# boosterpack.net
KiCad netlist of a schematic drawn in EAGLE
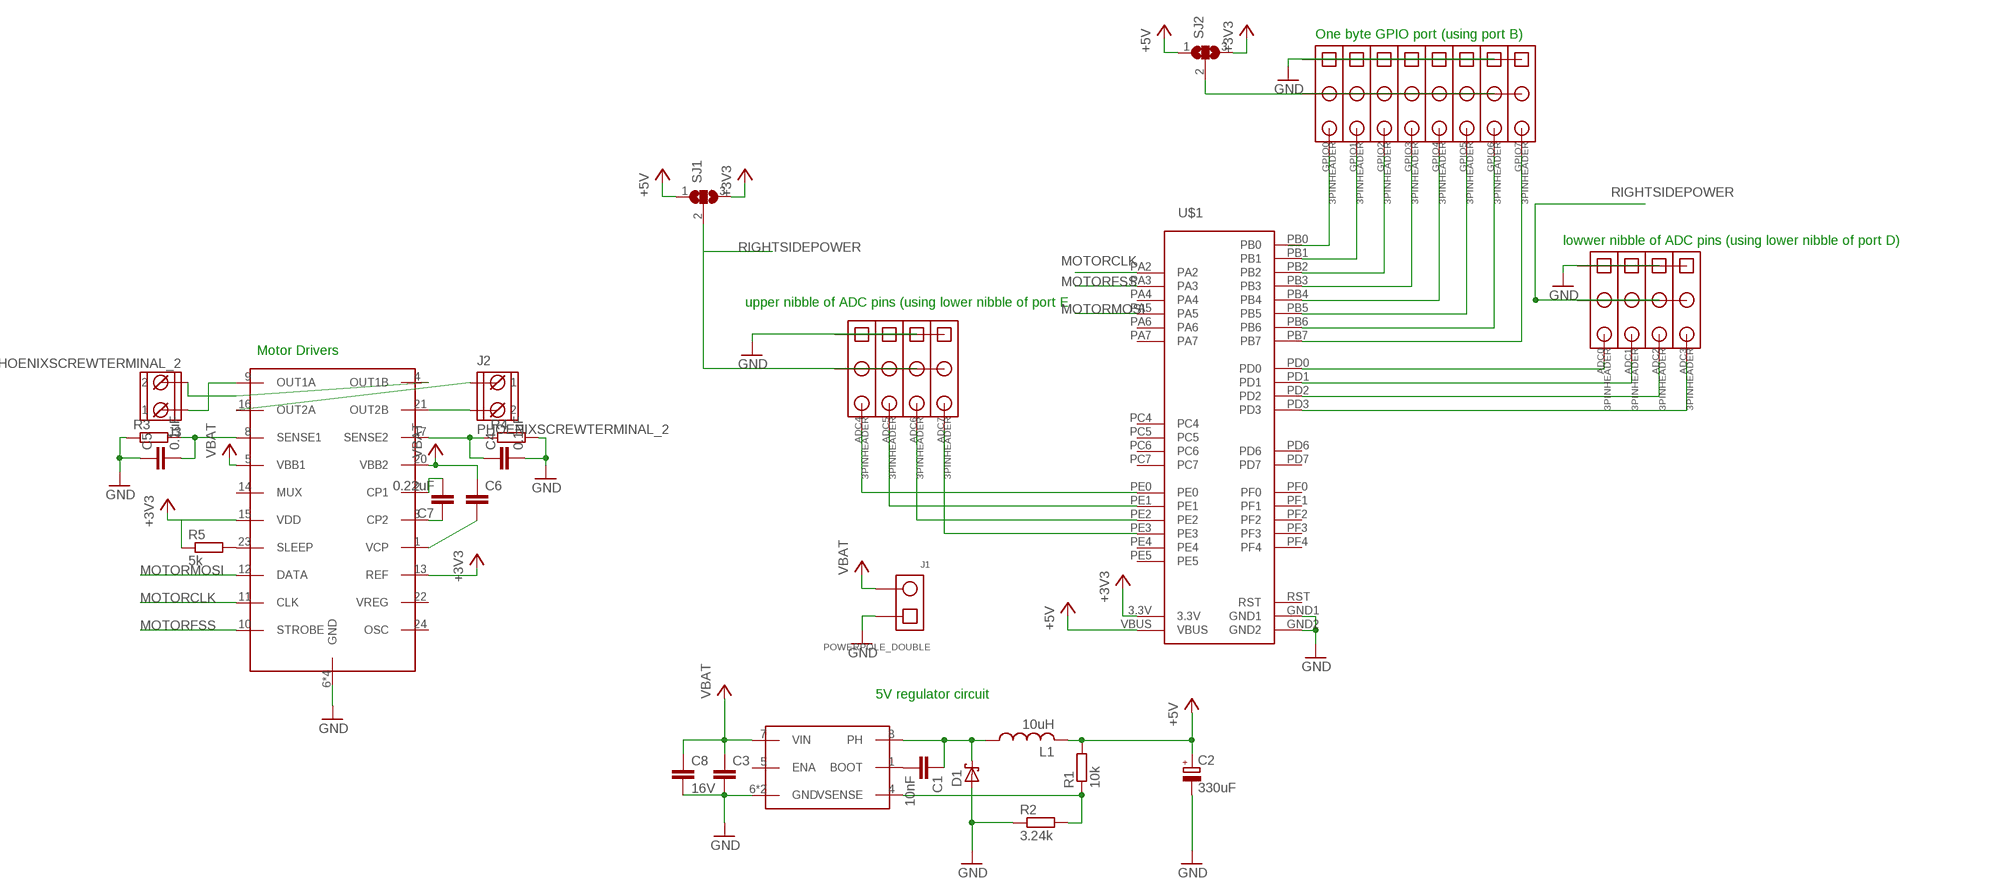
[diagram p0: schematic, sheet 1]

(export (version "E")
  (design (tool "Eeschema 10.0.6"))
  (components
    (comp (ref "ADC0")
      (value "3PINHEADER")
      (footprint "eagle-import:3PINHEADER")
      (libsource (lib "eagle-import") (part "3PINHEADER"))
    )
    (comp (ref "ADC1")
      (value "3PINHEADER")
      (footprint "eagle-import:3PINHEADER")
      (libsource (lib "eagle-import") (part "3PINHEADER"))
    )
    (comp (ref "ADC2")
      (value "3PINHEADER")
      (footprint "eagle-import:3PINHEADER")
      (libsource (lib "eagle-import") (part "3PINHEADER"))
    )
    (comp (ref "ADC3")
      (value "3PINHEADER")
      (footprint "eagle-import:3PINHEADER")
      (libsource (lib "eagle-import") (part "3PINHEADER"))
    )
    (comp (ref "ADC4")
      (value "3PINHEADER")
      (footprint "eagle-import:3PINHEADER")
      (libsource (lib "eagle-import") (part "3PINHEADER"))
    )
    (comp (ref "ADC5")
      (value "3PINHEADER")
      (footprint "eagle-import:3PINHEADER")
      (libsource (lib "eagle-import") (part "3PINHEADER"))
    )
    (comp (ref "ADC6")
      (value "3PINHEADER")
      (footprint "eagle-import:3PINHEADER")
      (libsource (lib "eagle-import") (part "3PINHEADER"))
    )
    (comp (ref "ADC7")
      (value "3PINHEADER")
      (footprint "eagle-import:3PINHEADER")
      (libsource (lib "eagle-import") (part "3PINHEADER"))
    )
    (comp (ref "C1")
      (value "10nF")
      (footprint "eagle-import:C025-024X044")
      (libsource (lib "eagle-import") (part "C-EU025-024X044"))
    )
    (comp (ref "C2")
      (value "330uF")
      (footprint "eagle-import:B45181B")
      (libsource (lib "eagle-import") (part "CPOL-EUB45181B"))
    )
    (comp (ref "C3")
      (value "C-EU025-024X044")
      (footprint "eagle-import:C025-024X044")
      (libsource (lib "eagle-import") (part "C-EU025-024X044"))
    )
    (comp (ref "C4")
      (value "0.1uF")
      (footprint "eagle-import:C025-025X050")
      (libsource (lib "eagle-import") (part "C-EU025-025X050"))
    )
    (comp (ref "C5")
      (value "0.1uF")
      (footprint "eagle-import:C025-025X050")
      (libsource (lib "eagle-import") (part "C-EU025-025X050"))
    )
    (comp (ref "C6")
      (value "C-EU025-025X050")
      (footprint "eagle-import:C025-025X050")
      (libsource (lib "eagle-import") (part "C-EU025-025X050"))
    )
    (comp (ref "C7")
      (value "0.22uF")
      (footprint "eagle-import:C025-024X044")
      (libsource (lib "eagle-import") (part "C-EU025-024X044"))
    )
    (comp (ref "C8")
      (value "16V")
      (footprint "eagle-import:C050-075X075")
      (libsource (lib "eagle-import") (part "C-EU050-075X075"))
    )
    (comp (ref "D1")
      (value "SCHOTTKY-DIODEDO201T15")
      (footprint "eagle-import:DO201T15")
      (libsource (lib "eagle-import") (part "SCHOTTKY-DIODEDO201T15"))
    )
    (comp (ref "GPIO0")
      (value "3PINHEADER")
      (footprint "eagle-import:3PINHEADER")
      (libsource (lib "eagle-import") (part "3PINHEADER"))
    )
    (comp (ref "GPIO1")
      (value "3PINHEADER")
      (footprint "eagle-import:3PINHEADER")
      (libsource (lib "eagle-import") (part "3PINHEADER"))
    )
    (comp (ref "GPIO2")
      (value "3PINHEADER")
      (footprint "eagle-import:3PINHEADER")
      (libsource (lib "eagle-import") (part "3PINHEADER"))
    )
    (comp (ref "GPIO3")
      (value "3PINHEADER")
      (footprint "eagle-import:3PINHEADER")
      (libsource (lib "eagle-import") (part "3PINHEADER"))
    )
    (comp (ref "GPIO4")
      (value "3PINHEADER")
      (footprint "eagle-import:3PINHEADER")
      (libsource (lib "eagle-import") (part "3PINHEADER"))
    )
    (comp (ref "GPIO5")
      (value "3PINHEADER")
      (footprint "eagle-import:3PINHEADER")
      (libsource (lib "eagle-import") (part "3PINHEADER"))
    )
    (comp (ref "GPIO6")
      (value "3PINHEADER")
      (footprint "eagle-import:3PINHEADER")
      (libsource (lib "eagle-import") (part "3PINHEADER"))
    )
    (comp (ref "GPIO7")
      (value "3PINHEADER")
      (footprint "eagle-import:3PINHEADER")
      (libsource (lib "eagle-import") (part "3PINHEADER"))
    )
    (comp (ref "J1")
      (value "POWERPOLE_DOUBLE")
      (footprint "eagle-import:POWERPOLE_DOUBLE")
      (libsource (lib "eagle-import") (part "POWERPOLE_DOUBLE"))
    )
    (comp (ref "J2")
      (value "PHOENIXSCREWTERMINAL_2")
      (footprint "eagle-import:PHOENIXSCREWTERMINAL_2")
      (libsource (lib "eagle-import") (part "PHOENIXSCREWTERMINAL_2"))
    )
    (comp (ref "J3")
      (value "PHOENIXSCREWTERMINAL_2")
      (footprint "eagle-import:PHOENIXSCREWTERMINAL_2")
      (libsource (lib "eagle-import") (part "PHOENIXSCREWTERMINAL_2"))
    )
    (comp (ref "L1")
      (value "10uH")
      (footprint "eagle-import:SDR1006")
      (libsource (lib "eagle-import") (part "SDR1006"))
    )
    (comp (ref "R1")
      (value "10k")
      (footprint "eagle-import:0204_7")
      (libsource (lib "eagle-import") (part "R-EU_0204/7"))
    )
    (comp (ref "R2")
      (value "3.24k")
      (footprint "eagle-import:0204_7")
      (libsource (lib "eagle-import") (part "R-EU_0204/7"))
    )
    (comp (ref "R3")
      (value "R-EU_0204/7")
      (footprint "eagle-import:0204_7")
      (libsource (lib "eagle-import") (part "R-EU_0204/7"))
    )
    (comp (ref "R4")
      (value "R-EU_0204/7")
      (footprint "eagle-import:0204_7")
      (libsource (lib "eagle-import") (part "R-EU_0204/7"))
    )
    (comp (ref "R5")
      (value "5k")
      (footprint "eagle-import:0204_7")
      (libsource (lib "eagle-import") (part "R-EU_0204/7"))
    )
    (comp (ref "SJ1")
      (value "SJ2W")
      (footprint "eagle-import:SJ_2")
      (libsource (lib "eagle-import") (part "SJ2W"))
    )
    (comp (ref "SJ2")
      (value "SJ2W")
      (footprint "eagle-import:SJ_2")
      (libsource (lib "eagle-import") (part "SJ2W"))
    )
    (comp (ref "U$1")
      (value "STELLARIS-LAUNCHPADSTELLARIS-LAUNCHPAD-XL")
      (footprint "eagle-import:LAUNCHPAD-XL")
      (libsource (lib "eagle-import") (part "STELLARIS-LAUNCHPADSTELLARIS-LAUNCHPAD-XL"))
    )
    (comp (ref "U$2")
      (value "TPS5450")
      (footprint "eagle-import:DDS")
      (libsource (lib "eagle-import") (part "TPS5450"))
    )
    (comp (ref "U$3")
      (value "A3992A")
      (footprint "eagle-import:DIP24")
      (libsource (lib "eagle-import") (part "A3992A"))
    )
  )
  (nets
    (net (code "1") (name "+3V3") (class "Default")
      (node (ref "R5") (pin "1") (pinfunction "1_1") (pintype "passive"))
      (node (ref "SJ1") (pin "3") (pinfunction "3_3") (pintype "passive"))
      (node (ref "SJ2") (pin "3") (pinfunction "3_3") (pintype "passive"))
      (node (ref "U$1") (pin "3.3V") (pinfunction "3.3V_3.3V") (pintype "power_in"))
      (node (ref "U$3") (pin "13") (pinfunction "REF_13") (pintype "bidirectional"))
      (node (ref "U$3") (pin "15") (pinfunction "VDD_15") (pintype "bidirectional"))
    )
    (net (code "2") (name "+5V") (class "Default")
      (node (ref "C2") (pin "+") (pinfunction "+_+") (pintype "passive"))
      (node (ref "L1") (pin "P$2") (pinfunction "2_P$2") (pintype "passive"))
      (node (ref "R1") (pin "2") (pinfunction "2_2") (pintype "passive"))
      (node (ref "SJ1") (pin "1") (pinfunction "1_1") (pintype "passive"))
      (node (ref "SJ2") (pin "1") (pinfunction "1_1") (pintype "passive"))
      (node (ref "U$1") (pin "VBUS") (pinfunction "VBUS_VBUS") (pintype "power_in"))
    )
    (net (code "3") (name "/MOTORCLK") (class "Default")
      (node (ref "U$1") (pin "PA2") (pinfunction "PA2_PA2") (pintype "bidirectional"))
      (node (ref "U$3") (pin "11") (pinfunction "CLK_11") (pintype "bidirectional"))
    )
    (net (code "4") (name "/MOTORFSS") (class "Default")
      (node (ref "U$1") (pin "PA3") (pinfunction "PA3_PA3") (pintype "bidirectional"))
      (node (ref "U$3") (pin "10") (pinfunction "STROBE_10") (pintype "bidirectional"))
    )
    (net (code "5") (name "/MOTORMOSI") (class "Default")
      (node (ref "U$1") (pin "PA5") (pinfunction "PA5_PA5") (pintype "bidirectional"))
      (node (ref "U$3") (pin "12") (pinfunction "DATA_12") (pintype "bidirectional"))
    )
    (net (code "6") (name "/RIGHTSIDEPOWER") (class "Default")
      (node (ref "ADC0") (pin "2") (pinfunction "2_2") (pintype "bidirectional"))
      (node (ref "ADC1") (pin "2") (pinfunction "2_2") (pintype "bidirectional"))
      (node (ref "ADC2") (pin "2") (pinfunction "2_2") (pintype "bidirectional"))
      (node (ref "ADC3") (pin "2") (pinfunction "2_2") (pintype "bidirectional"))
      (node (ref "ADC4") (pin "2") (pinfunction "2_2") (pintype "bidirectional"))
      (node (ref "ADC5") (pin "2") (pinfunction "2_2") (pintype "bidirectional"))
      (node (ref "ADC6") (pin "2") (pinfunction "2_2") (pintype "bidirectional"))
      (node (ref "ADC7") (pin "2") (pinfunction "2_2") (pintype "bidirectional"))
      (node (ref "SJ1") (pin "2") (pinfunction "2_2") (pintype "passive"))
    )
    (net (code "7") (name "/RST") (class "Default")
      (node (ref "U$1") (pin "RST") (pinfunction "RST_RST") (pintype "power_in"))
    )
    (net (code "8") (name "GND") (class "Default")
      (node (ref "ADC0") (pin "1") (pinfunction "1_1") (pintype "bidirectional"))
      (node (ref "ADC1") (pin "1") (pinfunction "1_1") (pintype "bidirectional"))
      (node (ref "ADC2") (pin "1") (pinfunction "1_1") (pintype "bidirectional"))
      (node (ref "ADC3") (pin "1") (pinfunction "1_1") (pintype "bidirectional"))
      (node (ref "ADC4") (pin "1") (pinfunction "1_1") (pintype "bidirectional"))
      (node (ref "ADC5") (pin "1") (pinfunction "1_1") (pintype "bidirectional"))
      (node (ref "ADC6") (pin "1") (pinfunction "1_1") (pintype "bidirectional"))
      (node (ref "ADC7") (pin "1") (pinfunction "1_1") (pintype "bidirectional"))
      (node (ref "C2") (pin "-") (pinfunction "-_-") (pintype "passive"))
      (node (ref "C3") (pin "2") (pinfunction "2_2") (pintype "passive"))
      (node (ref "C4") (pin "2") (pinfunction "2_2") (pintype "passive"))
      (node (ref "C5") (pin "1") (pinfunction "1_1") (pintype "passive"))
      (node (ref "C8") (pin "2") (pinfunction "2_2") (pintype "passive"))
      (node (ref "D1") (pin "A") (pinfunction "A_A") (pintype "passive"))
      (node (ref "GPIO0") (pin "1") (pinfunction "1_1") (pintype "bidirectional"))
      (node (ref "GPIO1") (pin "1") (pinfunction "1_1") (pintype "bidirectional"))
      (node (ref "GPIO2") (pin "1") (pinfunction "1_1") (pintype "bidirectional"))
      (node (ref "GPIO3") (pin "1") (pinfunction "1_1") (pintype "bidirectional"))
      (node (ref "GPIO4") (pin "1") (pinfunction "1_1") (pintype "bidirectional"))
      (node (ref "GPIO5") (pin "1") (pinfunction "1_1") (pintype "bidirectional"))
      (node (ref "GPIO6") (pin "1") (pinfunction "1_1") (pintype "bidirectional"))
      (node (ref "GPIO7") (pin "1") (pinfunction "1_1") (pintype "bidirectional"))
      (node (ref "J1") (pin "1") (pinfunction "1_1") (pintype "bidirectional"))
      (node (ref "R2") (pin "1") (pinfunction "1_1") (pintype "passive"))
      (node (ref "R3") (pin "1") (pinfunction "1_1") (pintype "passive"))
      (node (ref "R4") (pin "2") (pinfunction "2_2") (pintype "passive"))
      (node (ref "U$1") (pin "GND1") (pinfunction "GND1_GND1") (pintype "bidirectional"))
      (node (ref "U$1") (pin "GND2") (pinfunction "GND2_GND2") (pintype "power_in"))
      (node (ref "U$2") (pin "6") (pinfunction "GND_6") (pintype "bidirectional"))
      (node (ref "U$2") (pin "GROUNDPAD") (pinfunction "GND_GROUNDPAD") (pintype "bidirectional"))
      (node (ref "U$3") (pin "18") (pinfunction "GND_18") (pintype "bidirectional"))
      (node (ref "U$3") (pin "19") (pinfunction "GND_19") (pintype "bidirectional"))
      (node (ref "U$3") (pin "6") (pinfunction "GND_6") (pintype "bidirectional"))
      (node (ref "U$3") (pin "7") (pinfunction "GND_7") (pintype "bidirectional"))
    )
    (net (code "9") (name "Net-(ADC0-Pad3)") (class "Default")
      (node (ref "ADC0") (pin "3") (pinfunction "3_3") (pintype "bidirectional"))
      (node (ref "U$1") (pin "PD0") (pinfunction "PD0_PD0") (pintype "bidirectional"))
    )
    (net (code "10") (name "Net-(ADC1-Pad3)") (class "Default")
      (node (ref "ADC1") (pin "3") (pinfunction "3_3") (pintype "bidirectional"))
      (node (ref "U$1") (pin "PD1") (pinfunction "PD1_PD1") (pintype "bidirectional"))
    )
    (net (code "11") (name "Net-(ADC2-Pad3)") (class "Default")
      (node (ref "ADC2") (pin "3") (pinfunction "3_3") (pintype "bidirectional"))
      (node (ref "U$1") (pin "PD2") (pinfunction "PD2_PD2") (pintype "bidirectional"))
    )
    (net (code "12") (name "Net-(ADC3-Pad3)") (class "Default")
      (node (ref "ADC3") (pin "3") (pinfunction "3_3") (pintype "bidirectional"))
      (node (ref "U$1") (pin "PD3") (pinfunction "PD3_PD3") (pintype "bidirectional"))
    )
    (net (code "13") (name "Net-(ADC4-Pad3)") (class "Default")
      (node (ref "ADC4") (pin "3") (pinfunction "3_3") (pintype "bidirectional"))
      (node (ref "U$1") (pin "PE0") (pinfunction "PE0_PE0") (pintype "bidirectional"))
    )
    (net (code "14") (name "Net-(ADC5-Pad3)") (class "Default")
      (node (ref "ADC5") (pin "3") (pinfunction "3_3") (pintype "bidirectional"))
      (node (ref "U$1") (pin "PE1") (pinfunction "PE1_PE1") (pintype "bidirectional"))
    )
    (net (code "15") (name "Net-(ADC6-Pad3)") (class "Default")
      (node (ref "ADC6") (pin "3") (pinfunction "3_3") (pintype "bidirectional"))
      (node (ref "U$1") (pin "PE2") (pinfunction "PE2_PE2") (pintype "bidirectional"))
    )
    (net (code "16") (name "Net-(ADC7-Pad3)") (class "Default")
      (node (ref "ADC7") (pin "3") (pinfunction "3_3") (pintype "bidirectional"))
      (node (ref "U$1") (pin "PE3") (pinfunction "PE3_PE3") (pintype "bidirectional"))
    )
    (net (code "17") (name "Net-(GPIO0-Pad2)") (class "Default")
      (node (ref "GPIO0") (pin "2") (pinfunction "2_2") (pintype "bidirectional"))
      (node (ref "GPIO1") (pin "2") (pinfunction "2_2") (pintype "bidirectional"))
      (node (ref "GPIO2") (pin "2") (pinfunction "2_2") (pintype "bidirectional"))
      (node (ref "GPIO3") (pin "2") (pinfunction "2_2") (pintype "bidirectional"))
      (node (ref "GPIO4") (pin "2") (pinfunction "2_2") (pintype "bidirectional"))
      (node (ref "GPIO5") (pin "2") (pinfunction "2_2") (pintype "bidirectional"))
      (node (ref "GPIO6") (pin "2") (pinfunction "2_2") (pintype "bidirectional"))
      (node (ref "GPIO7") (pin "2") (pinfunction "2_2") (pintype "bidirectional"))
      (node (ref "SJ2") (pin "2") (pinfunction "2_2") (pintype "passive"))
    )
    (net (code "18") (name "Net-(GPIO0-Pad3)") (class "Default")
      (node (ref "GPIO0") (pin "3") (pinfunction "3_3") (pintype "bidirectional"))
      (node (ref "U$1") (pin "PB0") (pinfunction "PB0_PB0") (pintype "bidirectional"))
    )
    (net (code "19") (name "Net-(GPIO1-Pad3)") (class "Default")
      (node (ref "GPIO1") (pin "3") (pinfunction "3_3") (pintype "bidirectional"))
      (node (ref "U$1") (pin "PB1") (pinfunction "PB1_PB1") (pintype "bidirectional"))
    )
    (net (code "20") (name "Net-(GPIO2-Pad3)") (class "Default")
      (node (ref "GPIO2") (pin "3") (pinfunction "3_3") (pintype "bidirectional"))
      (node (ref "U$1") (pin "PB2") (pinfunction "PB2_PB2") (pintype "bidirectional"))
    )
    (net (code "21") (name "Net-(GPIO3-Pad3)") (class "Default")
      (node (ref "GPIO3") (pin "3") (pinfunction "3_3") (pintype "bidirectional"))
      (node (ref "U$1") (pin "PB3") (pinfunction "PB3_PB3") (pintype "bidirectional"))
    )
    (net (code "22") (name "Net-(GPIO4-Pad3)") (class "Default")
      (node (ref "GPIO4") (pin "3") (pinfunction "3_3") (pintype "bidirectional"))
      (node (ref "U$1") (pin "PB4") (pinfunction "PB4_PB4") (pintype "bidirectional"))
    )
    (net (code "23") (name "Net-(GPIO5-Pad3)") (class "Default")
      (node (ref "GPIO5") (pin "3") (pinfunction "3_3") (pintype "bidirectional"))
      (node (ref "U$1") (pin "PB5") (pinfunction "PB5_PB5") (pintype "bidirectional"))
    )
    (net (code "24") (name "Net-(GPIO6-Pad3)") (class "Default")
      (node (ref "GPIO6") (pin "3") (pinfunction "3_3") (pintype "bidirectional"))
      (node (ref "U$1") (pin "PB6") (pinfunction "PB6_PB6") (pintype "bidirectional"))
    )
    (net (code "25") (name "Net-(GPIO7-Pad3)") (class "Default")
      (node (ref "GPIO7") (pin "3") (pinfunction "3_3") (pintype "bidirectional"))
      (node (ref "U$1") (pin "PB7") (pinfunction "PB7_PB7") (pintype "bidirectional"))
    )
    (net (code "26") (name "Net-(L1-1)") (class "Default")
      (node (ref "C1") (pin "1") (pinfunction "1_1") (pintype "passive"))
      (node (ref "D1") (pin "C") (pinfunction "C_C") (pintype "passive"))
      (node (ref "L1") (pin "P$1") (pinfunction "1_P$1") (pintype "passive"))
      (node (ref "U$2") (pin "8") (pinfunction "PH_8") (pintype "bidirectional"))
    )
    (net (code "27") (name "Net-(U$2-BOOT)") (class "Default")
      (node (ref "C1") (pin "2") (pinfunction "2_2") (pintype "passive"))
      (node (ref "U$2") (pin "1") (pinfunction "BOOT_1") (pintype "bidirectional"))
    )
    (net (code "28") (name "Net-(U$2-VSENSE)") (class "Default")
      (node (ref "R1") (pin "1") (pinfunction "1_1") (pintype "passive"))
      (node (ref "R2") (pin "2") (pinfunction "2_2") (pintype "passive"))
      (node (ref "U$2") (pin "4") (pinfunction "VSENSE_4") (pintype "bidirectional"))
    )
    (net (code "29") (name "Net-(U$3-CP1)") (class "Default")
      (node (ref "C7") (pin "2") (pinfunction "2_2") (pintype "passive"))
      (node (ref "U$3") (pin "2") (pinfunction "CP1_2") (pintype "bidirectional"))
    )
    (net (code "30") (name "Net-(U$3-CP2)") (class "Default")
      (node (ref "C7") (pin "1") (pinfunction "1_1") (pintype "passive"))
      (node (ref "U$3") (pin "3") (pinfunction "CP2_3") (pintype "bidirectional"))
    )
    (net (code "31") (name "Net-(U$3-OUT1A)") (class "Default")
      (node (ref "J3") (pin "1") (pinfunction "1_1") (pintype "bidirectional"))
      (node (ref "U$3") (pin "9") (pinfunction "OUT1A_9") (pintype "bidirectional"))
    )
    (net (code "32") (name "Net-(U$3-OUT1B)") (class "Default")
      (node (ref "J3") (pin "2") (pinfunction "2_2") (pintype "bidirectional"))
      (node (ref "U$3") (pin "4") (pinfunction "OUT1B_4") (pintype "bidirectional"))
    )
    (net (code "33") (name "Net-(U$3-OUT2A)") (class "Default")
      (node (ref "J2") (pin "1") (pinfunction "1_1") (pintype "bidirectional"))
      (node (ref "U$3") (pin "16") (pinfunction "OUT2A_16") (pintype "bidirectional"))
    )
    (net (code "34") (name "Net-(U$3-OUT2B)") (class "Default")
      (node (ref "J2") (pin "2") (pinfunction "2_2") (pintype "bidirectional"))
      (node (ref "U$3") (pin "21") (pinfunction "OUT2B_21") (pintype "bidirectional"))
    )
    (net (code "35") (name "Net-(U$3-SENSE1)") (class "Default")
      (node (ref "C5") (pin "2") (pinfunction "2_2") (pintype "passive"))
      (node (ref "R3") (pin "2") (pinfunction "2_2") (pintype "passive"))
      (node (ref "U$3") (pin "8") (pinfunction "SENSE1_8") (pintype "bidirectional"))
    )
    (net (code "36") (name "Net-(U$3-SENSE2)") (class "Default")
      (node (ref "C4") (pin "1") (pinfunction "1_1") (pintype "passive"))
      (node (ref "R4") (pin "1") (pinfunction "1_1") (pintype "passive"))
      (node (ref "U$3") (pin "17") (pinfunction "SENSE2_17") (pintype "bidirectional"))
    )
    (net (code "37") (name "Net-(U$3-SLEEP)") (class "Default")
      (node (ref "R5") (pin "2") (pinfunction "2_2") (pintype "passive"))
      (node (ref "U$3") (pin "23") (pinfunction "SLEEP_23") (pintype "bidirectional"))
    )
    (net (code "38") (name "Net-(U$3-VCP)") (class "Default")
      (node (ref "C6") (pin "2") (pinfunction "2_2") (pintype "passive"))
      (node (ref "U$3") (pin "1") (pinfunction "VCP_1") (pintype "bidirectional"))
    )
    (net (code "39") (name "VBAT") (class "Default")
      (node (ref "C3") (pin "1") (pinfunction "1_1") (pintype "passive"))
      (node (ref "C6") (pin "1") (pinfunction "1_1") (pintype "passive"))
      (node (ref "C8") (pin "1") (pinfunction "1_1") (pintype "passive"))
      (node (ref "J1") (pin "2") (pinfunction "2_2") (pintype "bidirectional"))
      (node (ref "U$2") (pin "7") (pinfunction "VIN_7") (pintype "bidirectional"))
      (node (ref "U$3") (pin "20") (pinfunction "VBB2_20") (pintype "bidirectional"))
      (node (ref "U$3") (pin "5") (pinfunction "VBB1_5") (pintype "bidirectional"))
    )
    (net (code "40") (name "unconnected-(U$1-PadPA4)") (class "Default")
      (node (ref "U$1") (pin "PA4") (pinfunction "PA4_PA4") (pintype "bidirectional"))
    )
    (net (code "41") (name "unconnected-(U$1-PadPA6)") (class "Default")
      (node (ref "U$1") (pin "PA6") (pinfunction "PA6_PA6") (pintype "bidirectional"))
    )
    (net (code "42") (name "unconnected-(U$1-PadPA7)") (class "Default")
      (node (ref "U$1") (pin "PA7") (pinfunction "PA7_PA7") (pintype "bidirectional"))
    )
    (net (code "43") (name "unconnected-(U$1-PadPC4)") (class "Default")
      (node (ref "U$1") (pin "PC4") (pinfunction "PC4_PC4") (pintype "bidirectional"))
    )
    (net (code "44") (name "unconnected-(U$1-PadPC5)") (class "Default")
      (node (ref "U$1") (pin "PC5") (pinfunction "PC5_PC5") (pintype "bidirectional"))
    )
    (net (code "45") (name "unconnected-(U$1-PadPC6)") (class "Default")
      (node (ref "U$1") (pin "PC6") (pinfunction "PC6_PC6") (pintype "bidirectional"))
    )
    (net (code "46") (name "unconnected-(U$1-PadPC7)") (class "Default")
      (node (ref "U$1") (pin "PC7") (pinfunction "PC7_PC7") (pintype "bidirectional"))
    )
    (net (code "47") (name "unconnected-(U$1-PadPD6)") (class "Default")
      (node (ref "U$1") (pin "PD6") (pinfunction "PD6_PD6") (pintype "bidirectional"))
    )
    (net (code "48") (name "unconnected-(U$1-PadPD7)") (class "Default")
      (node (ref "U$1") (pin "PD7") (pinfunction "PD7_PD7") (pintype "bidirectional"))
    )
    (net (code "49") (name "unconnected-(U$1-PadPE4)") (class "Default")
      (node (ref "U$1") (pin "PE4") (pinfunction "PE4_PE4") (pintype "bidirectional"))
    )
    (net (code "50") (name "unconnected-(U$1-PadPE5)") (class "Default")
      (node (ref "U$1") (pin "PE5") (pinfunction "PE5_PE5") (pintype "bidirectional"))
    )
    (net (code "51") (name "unconnected-(U$1-PadPF0)") (class "Default")
      (node (ref "U$1") (pin "PF0") (pinfunction "PF0_PF0") (pintype "bidirectional"))
    )
    (net (code "52") (name "unconnected-(U$1-PadPF1)") (class "Default")
      (node (ref "U$1") (pin "PF1") (pinfunction "PF1_PF1") (pintype "bidirectional"))
    )
    (net (code "53") (name "unconnected-(U$1-PadPF2)") (class "Default")
      (node (ref "U$1") (pin "PF2") (pinfunction "PF2_PF2") (pintype "bidirectional"))
    )
    (net (code "54") (name "unconnected-(U$1-PadPF3)") (class "Default")
      (node (ref "U$1") (pin "PF3") (pinfunction "PF3_PF3") (pintype "bidirectional"))
    )
    (net (code "55") (name "unconnected-(U$1-PadPF4)") (class "Default")
      (node (ref "U$1") (pin "PF4") (pinfunction "PF4_PF4") (pintype "bidirectional"))
    )
    (net (code "56") (name "unconnected-(U$2-ENA-Pad5)") (class "Default")
      (node (ref "U$2") (pin "5") (pinfunction "ENA_5") (pintype "bidirectional"))
    )
    (net (code "57") (name "unconnected-(U$3-MUX-Pad14)") (class "Default")
      (node (ref "U$3") (pin "14") (pinfunction "MUX_14") (pintype "bidirectional"))
    )
    (net (code "58") (name "unconnected-(U$3-OSC-Pad24)") (class "Default")
      (node (ref "U$3") (pin "24") (pinfunction "OSC_24") (pintype "bidirectional"))
    )
    (net (code "59") (name "unconnected-(U$3-VREG-Pad22)") (class "Default")
      (node (ref "U$3") (pin "22") (pinfunction "VREG_22") (pintype "bidirectional"))
    )
  )
)
